# PI_R3_REV1_MCU.net
KiCad netlist of a schematic drawn in Altium Designer
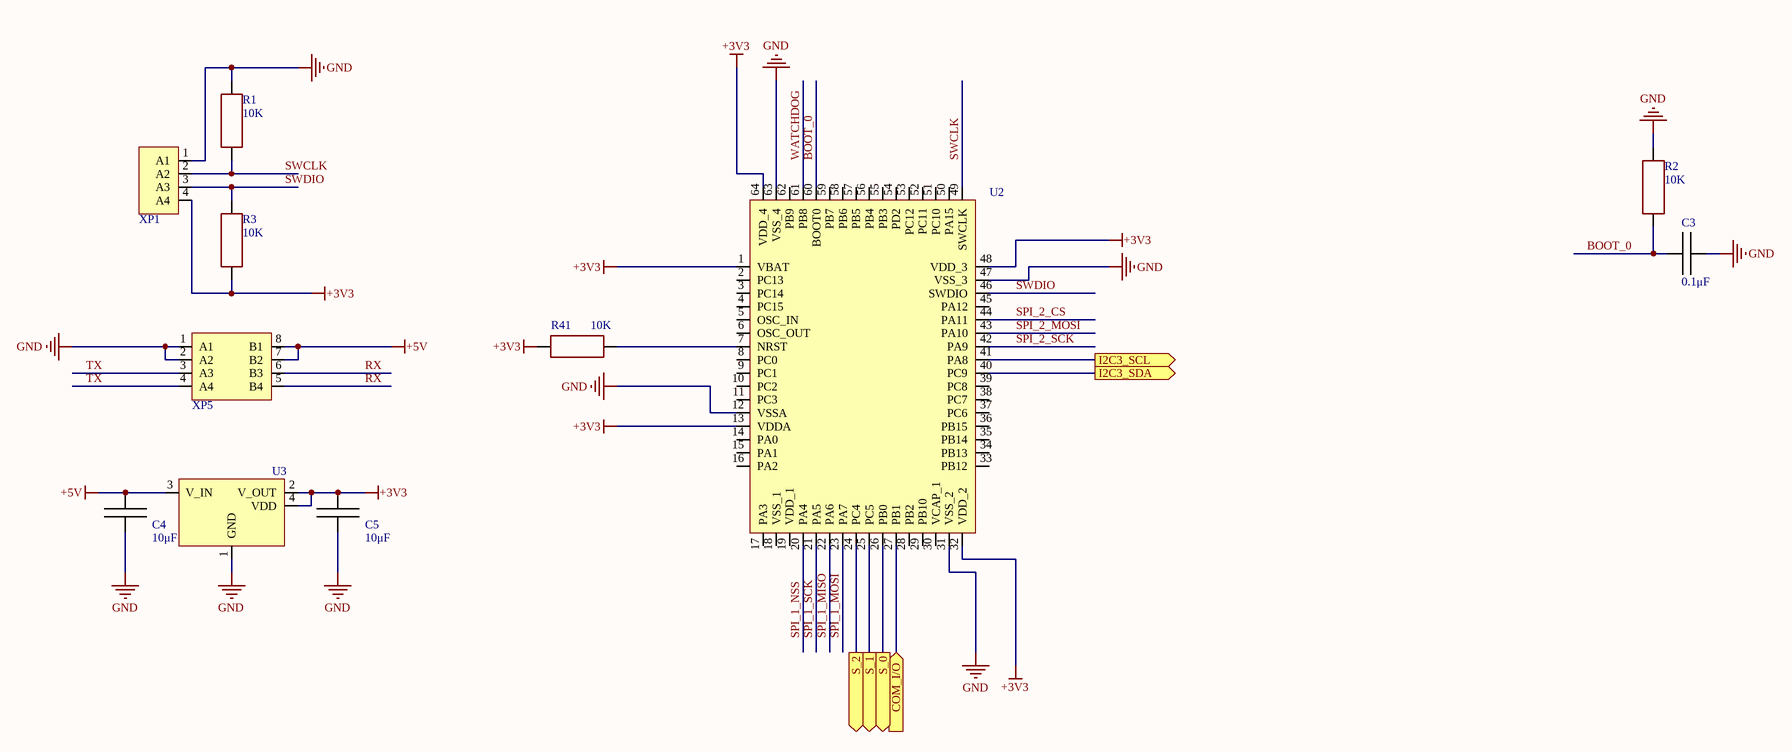
[diagram p0: PI_R3_REV1_MCU.SchDoc]

(export (version "E")
  (design (tool "Eeschema 10.0.6"))
  (components
    (comp (ref "C3")
      (value "0.1μF")
      (footprint "CAP: 0402")
      (fields (field (name "VOLTAGE") "??V") (field (name "Comment") "Cap_0402"))
      (libsource (lib "capacitor") (part "Cap_0402"))
    )
    (comp (ref "C4")
      (value "10μF")
      (footprint "CAP: 0805")
      (fields (field (name "VOLTAGE") "??V") (field (name "Comment") "Cap_0805"))
      (libsource (lib "capacitor") (part "Cap_0805"))
    )
    (comp (ref "C5")
      (value "10μF")
      (footprint "CAP: 0805")
      (fields (field (name "VOLTAGE") "??V") (field (name "Comment") "Cap_0805"))
      (libsource (lib "capacitor") (part "Cap_0805"))
    )
    (comp (ref "R1")
      (value "10K")
      (footprint "RES: 0402")
      (fields (field (name "TOLERANCE") "±5%"))
      (libsource (lib "") (part "Resistor_0402_2"))
    )
    (comp (ref "R2")
      (value "10K")
      (footprint "RES: 0402")
      (fields (field (name "TOLERANCE") "±5%"))
      (libsource (lib "resistor") (part "Resistor_0402"))
    )
    (comp (ref "R3")
      (value "10K")
      (footprint "RES: 0402")
      (fields (field (name "TOLERANCE") "±5%"))
      (libsource (lib "") (part "Resistor_0402_2"))
    )
    (comp (ref "R41")
      (value "10K")
      (footprint "RES: 0402")
      (fields (field (name "TOLERANCE") "±5%"))
      (libsource (lib "") (part "Resistor_0402_1"))
    )
    (comp (ref "U2")
      (value "STM32F413RGT6")
      (footprint "LQFP-64")
      (fields (field (name "MANUFACTURER") "STMicroelectronics"))
      (libsource (lib "MY_INT_LIB") (part "STM32F413RGT6"))
    )
    (comp (ref "U3")
      (value "LD1117S33CTR4")
      (footprint "SOT-223-3")
      (description "LDO Voltage Regulator 3.3V 0.8A Positive")
      (fields (field (name "MANUFACTURER") "STMicroelectronics"))
      (libsource (lib "MY_INT_LIB") (part "LD1117S33CTR"))
    )
    (comp (ref "XP1")
      (value "PLS-6 (DS1021-1x6)")
      (footprint "PLS-4 (DS1021-1x4)")
      (description "Board to Board, Surface Mount, Single row, 6 Positions, 2.54mm, Vertical.")
      (fields (field (name "MANUFACTURER") "Connfly"))
      (libsource (lib "MY_INT_LIB") (part "PLS-4 (DS1021-1x4)"))
    )
    (comp (ref "XP5")
      (value "55508-008TRLF")
      (footprint "55508-008TRLF")
      (description "Board to Board, Receptacle, Surface Mount, Double row, 8 Positions, 2mm (0.079inch), Vertical.")
      (fields (field (name "MANUFACTURER") "Amphenol FCI"))
      (libsource (lib "MY_INT_LIB") (part "55508-008TRLF"))
    )
  )
  (nets
    (net (code "1") (name "+3V3") (class "Default")
      (node (ref "C5") (pin "2") (pinfunction "2_2") (pintype "passive"))
      (node (ref "R3") (pin "1") (pinfunction "1_1") (pintype "passive"))
      (node (ref "R41") (pin "1") (pinfunction "1_1") (pintype "passive"))
      (node (ref "U2") (pin "1") (pinfunction "VBAT_1") (pintype "passive"))
      (node (ref "U2") (pin "13") (pinfunction "VDDA_13") (pintype "passive"))
      (node (ref "U2") (pin "32") (pinfunction "VDD_2_32") (pintype "passive"))
      (node (ref "U2") (pin "48") (pinfunction "VDD_3_48") (pintype "passive"))
      (node (ref "U2") (pin "64") (pinfunction "VDD_4_64") (pintype "passive"))
      (node (ref "U3") (pin "2") (pinfunction "V_OUT_2") (pintype "power_in"))
      (node (ref "U3") (pin "4") (pinfunction "VDD_4") (pintype "power_in"))
      (node (ref "XP1") (pin "4") (pinfunction "A4_4") (pintype "passive"))
    )
    (net (code "2") (name "+5V") (class "Default")
      (node (ref "C4") (pin "2") (pinfunction "2_2") (pintype "passive"))
      (node (ref "U3") (pin "3") (pinfunction "V_IN_3") (pintype "power_in"))
      (node (ref "XP5") (pin "7") (pinfunction "B2_7") (pintype "passive"))
      (node (ref "XP5") (pin "8") (pinfunction "B1_8") (pintype "passive"))
    )
    (net (code "3") (name "/BOOT_0") (class "Default")
      (node (ref "C3") (pin "2") (pinfunction "2_2") (pintype "passive"))
      (node (ref "R2") (pin "2") (pinfunction "2_2") (pintype "passive"))
      (node (ref "U2") (pin "60") (pinfunction "BOOT0_60") (pintype "passive"))
    )
    (net (code "4") (name "/COM_I{slash}O") (class "Default")
      (node (ref "U2") (pin "27") (pinfunction "PB1_27") (pintype "passive"))
    )
    (net (code "5") (name "/I2C3_SCL") (class "Default")
      (node (ref "U2") (pin "41") (pinfunction "PA8_41") (pintype "passive"))
    )
    (net (code "6") (name "/I2C3_SDA") (class "Default")
      (node (ref "U2") (pin "40") (pinfunction "PC9_40") (pintype "passive"))
    )
    (net (code "7") (name "/RX") (class "Default")
      (node (ref "XP5") (pin "5") (pinfunction "B4_5") (pintype "passive"))
      (node (ref "XP5") (pin "6") (pinfunction "B3_6") (pintype "passive"))
    )
    (net (code "8") (name "/SPI_1_MISO") (class "Default")
      (node (ref "U2") (pin "22") (pinfunction "PA6_22") (pintype "passive"))
    )
    (net (code "9") (name "/SPI_1_MOSI") (class "Default")
      (node (ref "U2") (pin "23") (pinfunction "PA7_23") (pintype "passive"))
    )
    (net (code "10") (name "/SPI_1_NSS") (class "Default")
      (node (ref "U2") (pin "20") (pinfunction "PA4_20") (pintype "passive"))
    )
    (net (code "11") (name "/SPI_1_SCK") (class "Default")
      (node (ref "U2") (pin "21") (pinfunction "PA5_21") (pintype "passive"))
    )
    (net (code "12") (name "/SPI_2_CS") (class "Default")
      (node (ref "U2") (pin "44") (pinfunction "PA11_44") (pintype "passive"))
    )
    (net (code "13") (name "/SPI_2_MOSI") (class "Default")
      (node (ref "U2") (pin "43") (pinfunction "PA10_43") (pintype "passive"))
    )
    (net (code "14") (name "/SPI_2_SCK") (class "Default")
      (node (ref "U2") (pin "42") (pinfunction "PA9_42") (pintype "passive"))
    )
    (net (code "15") (name "/SWCLK") (class "Default")
      (node (ref "R1") (pin "1") (pinfunction "1_1") (pintype "passive"))
      (node (ref "U2") (pin "49") (pinfunction "SWCLK_49") (pintype "passive"))
      (node (ref "XP1") (pin "2") (pinfunction "A2_2") (pintype "passive"))
    )
    (net (code "16") (name "/SWDIO") (class "Default")
      (node (ref "R3") (pin "2") (pinfunction "2_2") (pintype "passive"))
      (node (ref "U2") (pin "46") (pinfunction "SWDIO_46") (pintype "passive"))
      (node (ref "XP1") (pin "3") (pinfunction "A3_3") (pintype "passive"))
    )
    (net (code "17") (name "/S_0") (class "Default")
      (node (ref "U2") (pin "26") (pinfunction "PB0_26") (pintype "passive"))
    )
    (net (code "18") (name "/S_1") (class "Default")
      (node (ref "U2") (pin "25") (pinfunction "PC5_25") (pintype "passive"))
    )
    (net (code "19") (name "/S_2") (class "Default")
      (node (ref "U2") (pin "24") (pinfunction "PC4_24") (pintype "passive"))
    )
    (net (code "20") (name "/TX") (class "Default")
      (node (ref "XP5") (pin "3") (pinfunction "A3_3") (pintype "passive"))
      (node (ref "XP5") (pin "4") (pinfunction "A4_4") (pintype "passive"))
    )
    (net (code "21") (name "/WATCHDOG") (class "Default")
      (node (ref "U2") (pin "61") (pinfunction "PB8_61") (pintype "passive"))
    )
    (net (code "22") (name "GND") (class "Default")
      (node (ref "C3") (pin "1") (pinfunction "1_1") (pintype "passive"))
      (node (ref "C4") (pin "1") (pinfunction "1_1") (pintype "passive"))
      (node (ref "C5") (pin "1") (pinfunction "1_1") (pintype "passive"))
      (node (ref "R1") (pin "2") (pinfunction "2_2") (pintype "passive"))
      (node (ref "R2") (pin "1") (pinfunction "1_1") (pintype "passive"))
      (node (ref "U2") (pin "12") (pinfunction "VSSA_12") (pintype "passive"))
      (node (ref "U2") (pin "31") (pinfunction "VSS_2_31") (pintype "passive"))
      (node (ref "U2") (pin "47") (pinfunction "VSS_3_47") (pintype "passive"))
      (node (ref "U2") (pin "63") (pinfunction "VSS_4_63") (pintype "passive"))
      (node (ref "U3") (pin "1") (pinfunction "GND_1") (pintype "power_in"))
      (node (ref "XP1") (pin "1") (pinfunction "A1_1") (pintype "passive"))
      (node (ref "XP5") (pin "1") (pinfunction "A1_1") (pintype "passive"))
      (node (ref "XP5") (pin "2") (pinfunction "A2_2") (pintype "passive"))
    )
    (net (code "23") (name "Net-(U2-NRST)") (class "Default")
      (node (ref "R41") (pin "2") (pinfunction "2_2") (pintype "passive"))
      (node (ref "U2") (pin "7") (pinfunction "NRST_7") (pintype "passive"))
    )
    (net (code "24") (name "unconnected-(U2-OSC_IN-Pad5)") (class "Default")
      (node (ref "U2") (pin "5") (pinfunction "OSC_IN_5") (pintype "passive"))
    )
    (net (code "25") (name "unconnected-(U2-OSC_OUT-Pad6)") (class "Default")
      (node (ref "U2") (pin "6") (pinfunction "OSC_OUT_6") (pintype "passive"))
    )
    (net (code "26") (name "unconnected-(U2-PA0-Pad14)") (class "Default")
      (node (ref "U2") (pin "14") (pinfunction "PA0_14") (pintype "passive"))
    )
    (net (code "27") (name "unconnected-(U2-PA1-Pad15)") (class "Default")
      (node (ref "U2") (pin "15") (pinfunction "PA1_15") (pintype "passive"))
    )
    (net (code "28") (name "unconnected-(U2-PA2-Pad16)") (class "Default")
      (node (ref "U2") (pin "16") (pinfunction "PA2_16") (pintype "passive"))
    )
    (net (code "29") (name "unconnected-(U2-PA3-Pad17)") (class "Default")
      (node (ref "U2") (pin "17") (pinfunction "PA3_17") (pintype "passive"))
    )
    (net (code "30") (name "unconnected-(U2-PA12-Pad45)") (class "Default")
      (node (ref "U2") (pin "45") (pinfunction "PA12_45") (pintype "passive"))
    )
    (net (code "31") (name "unconnected-(U2-PA15-Pad50)") (class "Default")
      (node (ref "U2") (pin "50") (pinfunction "PA15_50") (pintype "passive"))
    )
    (net (code "32") (name "unconnected-(U2-PB2-Pad28)") (class "Default")
      (node (ref "U2") (pin "28") (pinfunction "PB2_28") (pintype "passive"))
    )
    (net (code "33") (name "unconnected-(U2-PB3-Pad55)") (class "Default")
      (node (ref "U2") (pin "55") (pinfunction "PB3_55") (pintype "passive"))
    )
    (net (code "34") (name "unconnected-(U2-PB4-Pad56)") (class "Default")
      (node (ref "U2") (pin "56") (pinfunction "PB4_56") (pintype "passive"))
    )
    (net (code "35") (name "unconnected-(U2-PB5-Pad57)") (class "Default")
      (node (ref "U2") (pin "57") (pinfunction "PB5_57") (pintype "passive"))
    )
    (net (code "36") (name "unconnected-(U2-PB6-Pad58)") (class "Default")
      (node (ref "U2") (pin "58") (pinfunction "PB6_58") (pintype "passive"))
    )
    (net (code "37") (name "unconnected-(U2-PB7-Pad59)") (class "Default")
      (node (ref "U2") (pin "59") (pinfunction "PB7_59") (pintype "passive"))
    )
    (net (code "38") (name "unconnected-(U2-PB9-Pad62)") (class "Default")
      (node (ref "U2") (pin "62") (pinfunction "PB9_62") (pintype "passive"))
    )
    (net (code "39") (name "unconnected-(U2-PB10-Pad29)") (class "Default")
      (node (ref "U2") (pin "29") (pinfunction "PB10_29") (pintype "passive"))
    )
    (net (code "40") (name "unconnected-(U2-PB12-Pad33)") (class "Default")
      (node (ref "U2") (pin "33") (pinfunction "PB12_33") (pintype "passive"))
    )
    (net (code "41") (name "unconnected-(U2-PB13-Pad34)") (class "Default")
      (node (ref "U2") (pin "34") (pinfunction "PB13_34") (pintype "passive"))
    )
    (net (code "42") (name "unconnected-(U2-PB14-Pad35)") (class "Default")
      (node (ref "U2") (pin "35") (pinfunction "PB14_35") (pintype "passive"))
    )
    (net (code "43") (name "unconnected-(U2-PB15-Pad36)") (class "Default")
      (node (ref "U2") (pin "36") (pinfunction "PB15_36") (pintype "passive"))
    )
    (net (code "44") (name "unconnected-(U2-PC0-Pad8)") (class "Default")
      (node (ref "U2") (pin "8") (pinfunction "PC0_8") (pintype "passive"))
    )
    (net (code "45") (name "unconnected-(U2-PC1-Pad9)") (class "Default")
      (node (ref "U2") (pin "9") (pinfunction "PC1_9") (pintype "passive"))
    )
    (net (code "46") (name "unconnected-(U2-PC2-Pad10)") (class "Default")
      (node (ref "U2") (pin "10") (pinfunction "PC2_10") (pintype "passive"))
    )
    (net (code "47") (name "unconnected-(U2-PC3-Pad11)") (class "Default")
      (node (ref "U2") (pin "11") (pinfunction "PC3_11") (pintype "passive"))
    )
    (net (code "48") (name "unconnected-(U2-PC6-Pad37)") (class "Default")
      (node (ref "U2") (pin "37") (pinfunction "PC6_37") (pintype "passive"))
    )
    (net (code "49") (name "unconnected-(U2-PC7-Pad38)") (class "Default")
      (node (ref "U2") (pin "38") (pinfunction "PC7_38") (pintype "passive"))
    )
    (net (code "50") (name "unconnected-(U2-PC8-Pad39)") (class "Default")
      (node (ref "U2") (pin "39") (pinfunction "PC8_39") (pintype "passive"))
    )
    (net (code "51") (name "unconnected-(U2-PC10-Pad51)") (class "Default")
      (node (ref "U2") (pin "51") (pinfunction "PC10_51") (pintype "passive"))
    )
    (net (code "52") (name "unconnected-(U2-PC11-Pad52)") (class "Default")
      (node (ref "U2") (pin "52") (pinfunction "PC11_52") (pintype "passive"))
    )
    (net (code "53") (name "unconnected-(U2-PC12-Pad53)") (class "Default")
      (node (ref "U2") (pin "53") (pinfunction "PC12_53") (pintype "passive"))
    )
    (net (code "54") (name "unconnected-(U2-PC13-Pad2)") (class "Default")
      (node (ref "U2") (pin "2") (pinfunction "PC13_2") (pintype "passive"))
    )
    (net (code "55") (name "unconnected-(U2-PC14-Pad3)") (class "Default")
      (node (ref "U2") (pin "3") (pinfunction "PC14_3") (pintype "passive"))
    )
    (net (code "56") (name "unconnected-(U2-PC15-Pad4)") (class "Default")
      (node (ref "U2") (pin "4") (pinfunction "PC15_4") (pintype "passive"))
    )
    (net (code "57") (name "unconnected-(U2-PD2-Pad54)") (class "Default")
      (node (ref "U2") (pin "54") (pinfunction "PD2_54") (pintype "passive"))
    )
    (net (code "58") (name "unconnected-(U2-VCAP_1-Pad30)") (class "Default")
      (node (ref "U2") (pin "30") (pinfunction "VCAP_1_30") (pintype "passive"))
    )
    (net (code "59") (name "unconnected-(U2-VDD_1-Pad19)") (class "Default")
      (node (ref "U2") (pin "19") (pinfunction "VDD_1_19") (pintype "passive"))
    )
    (net (code "60") (name "unconnected-(U2-VSS_1-Pad18)") (class "Default")
      (node (ref "U2") (pin "18") (pinfunction "VSS_1_18") (pintype "passive"))
    )
  )
)
